# STM32F1_CNC_HW.net
KiCad netlist of a schematic drawn in Altium Designer
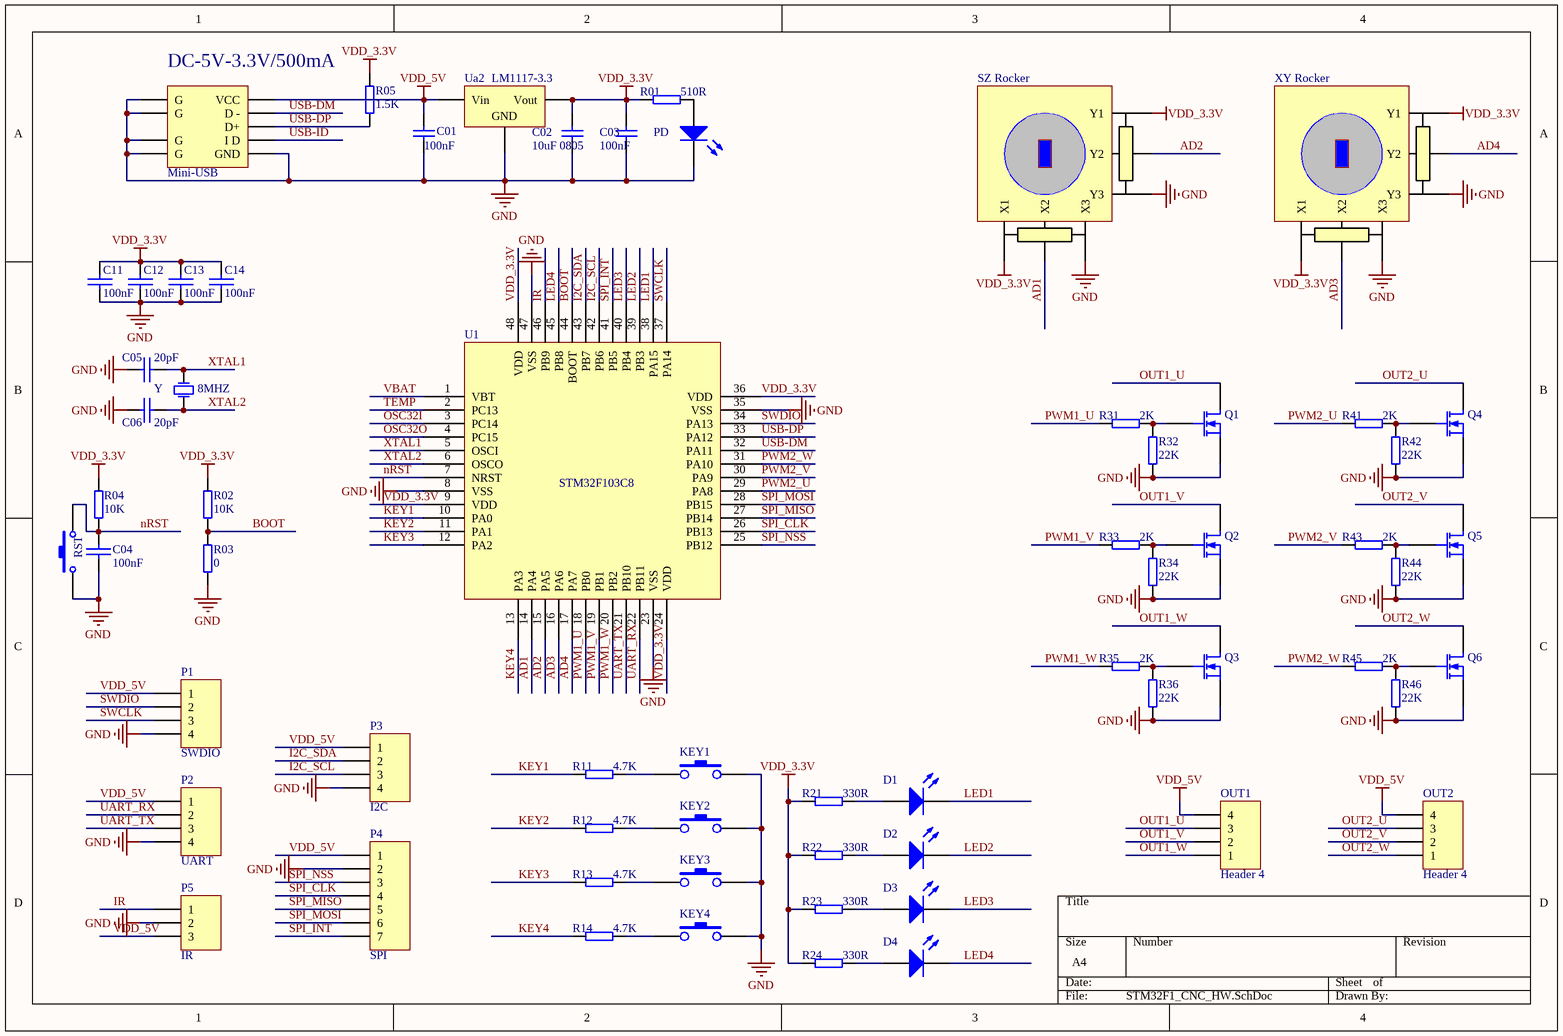
[diagram p0: STM32F1_CNC_HW.SchDoc]

(export (version "E")
  (design (tool "Eeschema 10.0.6"))
  (components
    (comp (ref "C01")
      (value "100nF")
      (footprint "0805")
      (description "0603  X5R")
      (fields (field (name "TOLERANCE") "10%"))
      (libsource (lib "MB963_1") (part "CAP SMD 0603  X5R 1礔 25V 10%"))
    )
    (comp (ref "C02")
      (value "10uF 0805")
      (footprint "0805")
      (description "0603  X5R 1礔")
      (fields (field (name "TOLERANCE") "10%"))
      (libsource (lib "MB963_1") (part "CAP SMD 0603  X5R 1礔 25V 10%"))
    )
    (comp (ref "C03")
      (value "100nF")
      (footprint "0603")
      (description "Capacitor 0402 / 0603 / 0805")
      (libsource (lib "MCD_TOOLS") (part "Capacitor_ST"))
    )
    (comp (ref "C04")
      (value "100nF")
      (footprint "0603")
      (description "Capacitor")
      (libsource (lib "wedolib") (part "CAP"))
    )
    (comp (ref "C05")
      (value "20pF")
      (footprint "0603")
      (description "Capacitor")
      (libsource (lib "wedolib") (part "CAP"))
    )
    (comp (ref "C06")
      (value "20pF")
      (footprint "0603")
      (description "Capacitor")
      (libsource (lib "wedolib") (part "CAP"))
    )
    (comp (ref "C11")
      (value "100nF")
      (footprint "0603")
      (description "Capacitor")
      (libsource (lib "WEDOLIB") (part "CAP"))
    )
    (comp (ref "C12")
      (value "100nF")
      (footprint "0603")
      (description "Capacitor")
      (libsource (lib "WEDOLIB") (part "CAP"))
    )
    (comp (ref "C13")
      (value "100nF")
      (footprint "0603")
      (description "Capacitor")
      (libsource (lib "WEDOLIB") (part "CAP"))
    )
    (comp (ref "C14")
      (value "100nF")
      (footprint "0603")
      (description "Capacitor")
      (libsource (lib "WEDOLIB") (part "CAP"))
    )
    (comp (ref "D1")
      (value "LED0")
      (footprint "LED-0603")
      (description "Typical INFRARED GaAs LED")
      (fields (field (name "PUBLISHER") "Altium Limited"))
      (libsource (lib "Miscellaneous Devices") (part "LED0"))
    )
    (comp (ref "D2")
      (value "LED0")
      (footprint "LED-0603")
      (description "Typical INFRARED GaAs LED")
      (fields (field (name "PUBLISHER") "Altium Limited"))
      (libsource (lib "Miscellaneous Devices") (part "LED0"))
    )
    (comp (ref "D3")
      (value "LED0")
      (footprint "LED-0603")
      (description "Typical INFRARED GaAs LED")
      (fields (field (name "PUBLISHER") "Altium Limited"))
      (libsource (lib "Miscellaneous Devices") (part "LED0"))
    )
    (comp (ref "D4")
      (value "LED0")
      (footprint "LED-0603")
      (description "Typical INFRARED GaAs LED")
      (fields (field (name "PUBLISHER") "Altium Limited"))
      (libsource (lib "Miscellaneous Devices") (part "LED0"))
    )
    (comp (ref "KEY1") (value "微动开关") (footprint "KeyB-6*6") (libsource (lib "STM32F1_CNC_HW") (part "微动开关")))
    (comp (ref "KEY2") (value "微动开关") (footprint "KeyB-6*6") (libsource (lib "STM32F1_CNC_HW") (part "微动开关")))
    (comp (ref "KEY3") (value "微动开关") (footprint "KeyB-6*6") (libsource (lib "STM32F1_CNC_HW") (part "微动开关")))
    (comp (ref "KEY4") (value "微动开关") (footprint "KeyB-6*6") (libsource (lib "STM32F1_CNC_HW") (part "微动开关")))
    (comp (ref "Mini-USB")
      (value "Mini-USB")
      (footprint "USB-mini-S")
      (libsource (lib "STM32F1_CNC_Schlib") (part "Mini-USB_G"))
    )
    (comp (ref "OUT1")
      (value "Header 4")
      (footprint "HDR-2.54-4P")
      (description "Header, 4-Pin")
      (fields (field (name "PUBLISHER") "Altium Limited"))
      (libsource (lib "") (part "Header 4_1"))
    )
    (comp (ref "OUT2")
      (value "Header 4")
      (footprint "HDR-2.54-4P")
      (description "Header, 4-Pin")
      (fields (field (name "PUBLISHER") "Altium Limited"))
      (libsource (lib "") (part "Header 4_1"))
    )
    (comp (ref "P1")
      (value "SWDIO")
      (footprint "HDR-2.54-4P")
      (description "Header, 4-Pin")
      (fields (field (name "PUBLISHER") "Altium Limited"))
      (libsource (lib "Miscellaneous Connectors") (part "Header 4"))
    )
    (comp (ref "P2")
      (value "UART")
      (footprint "HDR-2.54-4P")
      (description "Header, 4-Pin")
      (fields (field (name "PUBLISHER") "Altium Limited"))
      (libsource (lib "Miscellaneous Connectors") (part "Header 4"))
    )
    (comp (ref "P3")
      (value "I2C")
      (footprint "HDR-2.54-4P")
      (description "Header, 4-Pin")
      (fields (field (name "PUBLISHER") "Altium Limited"))
      (libsource (lib "Miscellaneous Connectors") (part "Header 4"))
    )
    (comp (ref "P4")
      (value "SPI")
      (footprint "HDR-2.54-7P")
      (description "Header, 7-Pin")
      (fields (field (name "PUBLISHER") "Altium Limited"))
      (libsource (lib "Miscellaneous Connectors") (part "Header 7"))
    )
    (comp (ref "P5")
      (value "IR")
      (footprint "IR-HS1838")
      (description "Header, 3-Pin")
      (fields (field (name "PUBLISHER") "Altium Limited"))
      (libsource (lib "Miscellaneous Connectors") (part "Header 3"))
    )
    (comp (ref "PD")
      (value "LED")
      (footprint "LED-0603")
      (description "Typical RED, GREEN, YELLOW, AMBER GaAs LED")
      (fields (field (name "PUBLISHER") "Altium Limited"))
      (libsource (lib "Miscellaneous Devices") (part "LED2"))
    )
    (comp (ref "Q1")
      (value "MOSFET-N")
      (footprint "SOT-23")
      (description "N-Channel MOSFET")
      (fields (field (name "PUBLISHER") "Altium Limited"))
      (libsource (lib "Miscellaneous Devices") (part "MOSFET-N"))
    )
    (comp (ref "Q2")
      (value "MOSFET-N")
      (footprint "SOT-23")
      (description "N-Channel MOSFET")
      (fields (field (name "PUBLISHER") "Altium Limited"))
      (libsource (lib "Miscellaneous Devices") (part "MOSFET-N"))
    )
    (comp (ref "Q3")
      (value "MOSFET-N")
      (footprint "SOT-23")
      (description "N-Channel MOSFET")
      (fields (field (name "PUBLISHER") "Altium Limited"))
      (libsource (lib "Miscellaneous Devices") (part "MOSFET-N"))
    )
    (comp (ref "Q4")
      (value "MOSFET-N")
      (footprint "SOT-23")
      (description "N-Channel MOSFET")
      (fields (field (name "PUBLISHER") "Altium Limited"))
      (libsource (lib "Miscellaneous Devices") (part "MOSFET-N"))
    )
    (comp (ref "Q5")
      (value "MOSFET-N")
      (footprint "SOT-23")
      (description "N-Channel MOSFET")
      (fields (field (name "PUBLISHER") "Altium Limited"))
      (libsource (lib "Miscellaneous Devices") (part "MOSFET-N"))
    )
    (comp (ref "Q6")
      (value "MOSFET-N")
      (footprint "SOT-23")
      (description "N-Channel MOSFET")
      (fields (field (name "PUBLISHER") "Altium Limited"))
      (libsource (lib "Miscellaneous Devices") (part "MOSFET-N"))
    )
    (comp (ref "R01")
      (value "510R")
      (footprint "0603")
      (description "Resister")
      (libsource (lib "WEDOLIB") (part "RES1"))
    )
    (comp (ref "R02")
      (value "10K")
      (footprint "0603")
      (description "Resister")
      (libsource (lib "WEDOLIB") (part "RES1"))
    )
    (comp (ref "R03")
      (value "0")
      (footprint "0603")
      (description "Resister")
      (libsource (lib "WEDOLIB") (part "RES1"))
    )
    (comp (ref "R04")
      (value "10K")
      (footprint "0603")
      (description "Resister")
      (libsource (lib "wedolib") (part "RES1"))
    )
    (comp (ref "R05")
      (value "1.5K")
      (footprint "0603")
      (description "Resister")
      (libsource (lib "wedolib") (part "RES1"))
    )
    (comp (ref "R11")
      (value "4.7K")
      (footprint "0603")
      (description "Resister")
      (libsource (lib "WEDOLIB") (part "RES1"))
    )
    (comp (ref "R12")
      (value "4.7K")
      (footprint "0603")
      (description "Resister")
      (libsource (lib "WEDOLIB") (part "RES1"))
    )
    (comp (ref "R13")
      (value "4.7K")
      (footprint "0603")
      (description "Resister")
      (libsource (lib "WEDOLIB") (part "RES1"))
    )
    (comp (ref "R14")
      (value "4.7K")
      (footprint "0603")
      (description "Resister")
      (libsource (lib "WEDOLIB") (part "RES1"))
    )
    (comp (ref "R21")
      (value "330R")
      (footprint "0603")
      (description "Resister")
      (libsource (lib "WEDOLIB") (part "RES1"))
    )
    (comp (ref "R22")
      (value "330R")
      (footprint "0603")
      (description "Resister")
      (libsource (lib "WEDOLIB") (part "RES1"))
    )
    (comp (ref "R23")
      (value "330R")
      (footprint "0603")
      (description "Resister")
      (libsource (lib "WEDOLIB") (part "RES1"))
    )
    (comp (ref "R24")
      (value "330R")
      (footprint "0603")
      (description "Resister")
      (libsource (lib "WEDOLIB") (part "RES1"))
    )
    (comp (ref "R31")
      (value "2K")
      (footprint "0603")
      (description "Resister")
      (libsource (lib "WEDOLIB") (part "RES1"))
    )
    (comp (ref "R32")
      (value "22K")
      (footprint "0603")
      (description "Resister")
      (libsource (lib "WEDOLIB") (part "RES1"))
    )
    (comp (ref "R33")
      (value "2K")
      (footprint "0603")
      (description "Resister")
      (libsource (lib "WEDOLIB") (part "RES1"))
    )
    (comp (ref "R34")
      (value "22K")
      (footprint "0603")
      (description "Resister")
      (libsource (lib "WEDOLIB") (part "RES1"))
    )
    (comp (ref "R35")
      (value "2K")
      (footprint "0603")
      (description "Resister")
      (libsource (lib "WEDOLIB") (part "RES1"))
    )
    (comp (ref "R36")
      (value "22K")
      (footprint "0603")
      (description "Resister")
      (libsource (lib "WEDOLIB") (part "RES1"))
    )
    (comp (ref "R41")
      (value "2K")
      (footprint "0603")
      (description "Resister")
      (libsource (lib "WEDOLIB") (part "RES1"))
    )
    (comp (ref "R42")
      (value "22K")
      (footprint "0603")
      (description "Resister")
      (libsource (lib "WEDOLIB") (part "RES1"))
    )
    (comp (ref "R43")
      (value "2K")
      (footprint "0603")
      (description "Resister")
      (libsource (lib "WEDOLIB") (part "RES1"))
    )
    (comp (ref "R44")
      (value "22K")
      (footprint "0603")
      (description "Resister")
      (libsource (lib "WEDOLIB") (part "RES1"))
    )
    (comp (ref "R45")
      (value "2K")
      (footprint "0603")
      (description "Resister")
      (libsource (lib "WEDOLIB") (part "RES1"))
    )
    (comp (ref "R46")
      (value "22K")
      (footprint "0603")
      (description "Resister")
      (libsource (lib "WEDOLIB") (part "RES1"))
    )
    (comp (ref "RST")
      (value "SW-PB")
      (footprint "RST-6*6")
      (description "Switch")
      (fields (field (name "PUBLISHER") "Altium Limited"))
      (libsource (lib "Miscellaneous Devices") (part "SW-PB"))
    )
    (comp (ref "SZ Rocker")
      (value "XY Rocker")
      (footprint "XY Rocker")
      (libsource (lib "STM32F1_CNC_HW") (part "XY Rocker"))
    )
    (comp (ref "U1")
      (value "STM32F103C8")
      (footprint "QFP48")
      (libsource (lib "STM32F1_CNC_HW") (part "STM32F103C8"))
    )
    (comp (ref "Ua2")
      (value "LM1117-3.3")
      (footprint "SOT223")
      (description "Voltage Regulator")
      (fields (field (name "PUBLISHER") "Altium Limited"))
      (libsource (lib "Miscellaneous Devices") (part "Volt Reg"))
    )
    (comp (ref "XY Rocker")
      (value "XY Rocker")
      (footprint "XY Rocker")
      (libsource (lib "STM32F1_CNC_HW") (part "XY Rocker"))
    )
    (comp (ref "Y")
      (value "8MHZ")
      (footprint "XTAL-3215-3P")
      (description "Crystal Oscillator")
      (fields (field (name "PUBLISHER") "Altium Limited"))
      (libsource (lib "*") (part "ECS-10-13-1"))
    )
  )
  (nets
    (net (code "1") (name "/AD1") (class "Default")
      (node (ref "SZ Rocker") (pin "X2") (pinfunction "X2_X2") (pintype "passive"))
      (node (ref "U1") (pin "14") (pinfunction "PA4_14") (pintype "passive"))
    )
    (net (code "2") (name "/AD2") (class "Default")
      (node (ref "SZ Rocker") (pin "Y2") (pinfunction "Y2_Y2") (pintype "passive"))
      (node (ref "U1") (pin "15") (pinfunction "PA5_15") (pintype "passive"))
    )
    (net (code "3") (name "/AD3") (class "Default")
      (node (ref "U1") (pin "16") (pinfunction "PA6_16") (pintype "passive"))
      (node (ref "XY Rocker") (pin "X2") (pinfunction "X2_X2") (pintype "passive"))
    )
    (net (code "4") (name "/AD4") (class "Default")
      (node (ref "U1") (pin "17") (pinfunction "PA7_17") (pintype "passive"))
      (node (ref "XY Rocker") (pin "Y2") (pinfunction "Y2_Y2") (pintype "passive"))
    )
    (net (code "5") (name "/BOOT") (class "Default")
      (node (ref "R02") (pin "2") (pinfunction "2_2") (pintype "passive"))
      (node (ref "R03") (pin "1") (pinfunction "1_1") (pintype "passive"))
      (node (ref "U1") (pin "44") (pinfunction "BOOT_44") (pintype "passive"))
    )
    (net (code "6") (name "/I2C_SCL") (class "Default")
      (node (ref "P3") (pin "3") (pinfunction "3_3") (pintype "passive"))
      (node (ref "U1") (pin "42") (pinfunction "PB6_42") (pintype "passive"))
    )
    (net (code "7") (name "/I2C_SDA") (class "Default")
      (node (ref "P3") (pin "2") (pinfunction "2_2") (pintype "passive"))
      (node (ref "U1") (pin "43") (pinfunction "PB7_43") (pintype "passive"))
    )
    (net (code "8") (name "/IR") (class "Default")
      (node (ref "P5") (pin "1") (pinfunction "1_1") (pintype "passive"))
      (node (ref "U1") (pin "46") (pinfunction "PB9_46") (pintype "passive"))
    )
    (net (code "9") (name "/KEY1") (class "Default")
      (node (ref "R11") (pin "1") (pinfunction "1_1") (pintype "passive"))
      (node (ref "U1") (pin "10") (pinfunction "PA0_10") (pintype "passive"))
    )
    (net (code "10") (name "/KEY2") (class "Default")
      (node (ref "R12") (pin "1") (pinfunction "1_1") (pintype "passive"))
      (node (ref "U1") (pin "11") (pinfunction "PA1_11") (pintype "passive"))
    )
    (net (code "11") (name "/KEY3") (class "Default")
      (node (ref "R13") (pin "1") (pinfunction "1_1") (pintype "passive"))
      (node (ref "U1") (pin "12") (pinfunction "PA2_12") (pintype "passive"))
    )
    (net (code "12") (name "/KEY4") (class "Default")
      (node (ref "R14") (pin "1") (pinfunction "1_1") (pintype "passive"))
      (node (ref "U1") (pin "13") (pinfunction "PA3_13") (pintype "passive"))
    )
    (net (code "13") (name "/LED1") (class "Default")
      (node (ref "D1") (pin "2") (pinfunction "K_2") (pintype "passive"))
      (node (ref "U1") (pin "38") (pinfunction "PA15_38") (pintype "passive"))
    )
    (net (code "14") (name "/LED2") (class "Default")
      (node (ref "D2") (pin "2") (pinfunction "K_2") (pintype "passive"))
      (node (ref "U1") (pin "39") (pinfunction "PB3_39") (pintype "passive"))
    )
    (net (code "15") (name "/LED3") (class "Default")
      (node (ref "D3") (pin "2") (pinfunction "K_2") (pintype "passive"))
      (node (ref "U1") (pin "40") (pinfunction "PB4_40") (pintype "passive"))
    )
    (net (code "16") (name "/LED4") (class "Default")
      (node (ref "D4") (pin "2") (pinfunction "K_2") (pintype "passive"))
      (node (ref "U1") (pin "45") (pinfunction "PB8_45") (pintype "passive"))
    )
    (net (code "17") (name "/OSC32I") (class "Default")
      (node (ref "U1") (pin "3") (pinfunction "PC14_3") (pintype "passive"))
    )
    (net (code "18") (name "/OSC32O") (class "Default")
      (node (ref "U1") (pin "4") (pinfunction "PC15_4") (pintype "passive"))
    )
    (net (code "19") (name "/OUT1_U") (class "Default")
      (node (ref "OUT1") (pin "3") (pinfunction "3_3") (pintype "passive"))
      (node (ref "Q1") (pin "3") (pinfunction "D_3") (pintype "passive"))
    )
    (net (code "20") (name "/OUT1_V") (class "Default")
      (node (ref "OUT1") (pin "2") (pinfunction "2_2") (pintype "passive"))
      (node (ref "Q2") (pin "3") (pinfunction "D_3") (pintype "passive"))
    )
    (net (code "21") (name "/OUT1_W") (class "Default")
      (node (ref "OUT1") (pin "1") (pinfunction "1_1") (pintype "passive"))
      (node (ref "Q3") (pin "3") (pinfunction "D_3") (pintype "passive"))
    )
    (net (code "22") (name "/OUT2_U") (class "Default")
      (node (ref "OUT2") (pin "3") (pinfunction "3_3") (pintype "passive"))
      (node (ref "Q4") (pin "3") (pinfunction "D_3") (pintype "passive"))
    )
    (net (code "23") (name "/OUT2_V") (class "Default")
      (node (ref "OUT2") (pin "2") (pinfunction "2_2") (pintype "passive"))
      (node (ref "Q5") (pin "3") (pinfunction "D_3") (pintype "passive"))
    )
    (net (code "24") (name "/OUT2_W") (class "Default")
      (node (ref "OUT2") (pin "1") (pinfunction "1_1") (pintype "passive"))
      (node (ref "Q6") (pin "3") (pinfunction "D_3") (pintype "passive"))
    )
    (net (code "25") (name "/PWM1_U") (class "Default")
      (node (ref "R31") (pin "1") (pinfunction "1_1") (pintype "passive"))
      (node (ref "U1") (pin "18") (pinfunction "PB0_18") (pintype "passive"))
    )
    (net (code "26") (name "/PWM1_V") (class "Default")
      (node (ref "R33") (pin "1") (pinfunction "1_1") (pintype "passive"))
      (node (ref "U1") (pin "19") (pinfunction "PB1_19") (pintype "passive"))
    )
    (net (code "27") (name "/PWM1_W") (class "Default")
      (node (ref "R35") (pin "1") (pinfunction "1_1") (pintype "passive"))
      (node (ref "U1") (pin "20") (pinfunction "PB2_20") (pintype "passive"))
    )
    (net (code "28") (name "/PWM2_U") (class "Default")
      (node (ref "R41") (pin "1") (pinfunction "1_1") (pintype "passive"))
      (node (ref "U1") (pin "29") (pinfunction "PA8_29") (pintype "passive"))
    )
    (net (code "29") (name "/PWM2_V") (class "Default")
      (node (ref "R43") (pin "1") (pinfunction "1_1") (pintype "passive"))
      (node (ref "U1") (pin "30") (pinfunction "PA9_30") (pintype "passive"))
    )
    (net (code "30") (name "/PWM2_W") (class "Default")
      (node (ref "R45") (pin "1") (pinfunction "1_1") (pintype "passive"))
      (node (ref "U1") (pin "31") (pinfunction "PA10_31") (pintype "passive"))
    )
    (net (code "31") (name "/SPI_CLK") (class "Default")
      (node (ref "P4") (pin "4") (pinfunction "4_4") (pintype "passive"))
      (node (ref "U1") (pin "26") (pinfunction "PB13_26") (pintype "passive"))
    )
    (net (code "32") (name "/SPI_INT") (class "Default")
      (node (ref "P4") (pin "7") (pinfunction "7_7") (pintype "passive"))
      (node (ref "U1") (pin "41") (pinfunction "PB5_41") (pintype "passive"))
    )
    (net (code "33") (name "/SPI_MISO") (class "Default")
      (node (ref "P4") (pin "5") (pinfunction "5_5") (pintype "passive"))
      (node (ref "U1") (pin "27") (pinfunction "PB14_27") (pintype "passive"))
    )
    (net (code "34") (name "/SPI_MOSI") (class "Default")
      (node (ref "P4") (pin "6") (pinfunction "6_6") (pintype "passive"))
      (node (ref "U1") (pin "28") (pinfunction "PB15_28") (pintype "passive"))
    )
    (net (code "35") (name "/SPI_NSS") (class "Default")
      (node (ref "P4") (pin "3") (pinfunction "3_3") (pintype "passive"))
      (node (ref "U1") (pin "25") (pinfunction "PB12_25") (pintype "passive"))
    )
    (net (code "36") (name "/SWCLK") (class "Default")
      (node (ref "P1") (pin "3") (pinfunction "3_3") (pintype "passive"))
      (node (ref "U1") (pin "37") (pinfunction "PA14_37") (pintype "passive"))
    )
    (net (code "37") (name "/SWDIO") (class "Default")
      (node (ref "P1") (pin "2") (pinfunction "2_2") (pintype "passive"))
      (node (ref "U1") (pin "34") (pinfunction "PA13_34") (pintype "passive"))
    )
    (net (code "38") (name "/TEMP") (class "Default")
      (node (ref "U1") (pin "2") (pinfunction "PC13_2") (pintype "passive"))
    )
    (net (code "39") (name "/UART_RX") (class "Default")
      (node (ref "P2") (pin "2") (pinfunction "2_2") (pintype "passive"))
      (node (ref "U1") (pin "22") (pinfunction "PB11_22") (pintype "passive"))
    )
    (net (code "40") (name "/UART_TX") (class "Default")
      (node (ref "P2") (pin "3") (pinfunction "3_3") (pintype "passive"))
      (node (ref "U1") (pin "21") (pinfunction "PB10_21") (pintype "passive"))
    )
    (net (code "41") (name "/USB-DM") (class "Default")
      (node (ref "Mini-USB") (pin "2") (pinfunction "D_-_2") (pintype "passive"))
      (node (ref "U1") (pin "32") (pinfunction "PA11_32") (pintype "passive"))
    )
    (net (code "42") (name "/USB-DP") (class "Default")
      (node (ref "Mini-USB") (pin "3") (pinfunction "D+_3") (pintype "passive"))
      (node (ref "R05") (pin "2") (pinfunction "2_2") (pintype "passive"))
      (node (ref "U1") (pin "33") (pinfunction "PA12_33") (pintype "passive"))
    )
    (net (code "43") (name "/USB-ID") (class "Default")
      (node (ref "Mini-USB") (pin "4") (pinfunction "I_D_4") (pintype "passive"))
    )
    (net (code "44") (name "/VBAT") (class "Default")
      (node (ref "U1") (pin "1") (pinfunction "VBT_1") (pintype "passive"))
    )
    (net (code "45") (name "/XTAL1") (class "Default")
      (node (ref "C05") (pin "2") (pinfunction "2_2") (pintype "passive"))
      (node (ref "U1") (pin "5") (pinfunction "OSCI_5") (pintype "passive"))
      (node (ref "Y") (pin "3") (pinfunction "OSC2_3") (pintype "passive"))
    )
    (net (code "46") (name "/XTAL2") (class "Default")
      (node (ref "C06") (pin "2") (pinfunction "2_2") (pintype "passive"))
      (node (ref "U1") (pin "6") (pinfunction "OSCO_6") (pintype "passive"))
      (node (ref "Y") (pin "1") (pinfunction "OSC1_1") (pintype "passive"))
    )
    (net (code "47") (name "/nRST") (class "Default")
      (node (ref "C04") (pin "1") (pinfunction "1_1") (pintype "passive"))
      (node (ref "R04") (pin "2") (pinfunction "2_2") (pintype "passive"))
      (node (ref "RST") (pin "1") (pinfunction "1_1") (pintype "passive"))
      (node (ref "U1") (pin "7") (pinfunction "NRST_7") (pintype "passive"))
    )
    (net (code "48") (name "GND") (class "Default")
      (node (ref "C01") (pin "1") (pinfunction "1_1") (pintype "passive"))
      (node (ref "C02") (pin "2") (pinfunction "2_2") (pintype "passive"))
      (node (ref "C03") (pin "1") (pinfunction "1_1") (pintype "passive"))
      (node (ref "C04") (pin "2") (pinfunction "2_2") (pintype "passive"))
      (node (ref "C05") (pin "1") (pinfunction "1_1") (pintype "passive"))
      (node (ref "C06") (pin "1") (pinfunction "1_1") (pintype "passive"))
      (node (ref "C11") (pin "2") (pinfunction "2_2") (pintype "passive"))
      (node (ref "C12") (pin "2") (pinfunction "2_2") (pintype "passive"))
      (node (ref "C13") (pin "2") (pinfunction "2_2") (pintype "passive"))
      (node (ref "C14") (pin "2") (pinfunction "2_2") (pintype "passive"))
      (node (ref "KEY1") (pin "2") (pinfunction "2_2") (pintype "passive"))
      (node (ref "KEY2") (pin "2") (pinfunction "2_2") (pintype "passive"))
      (node (ref "KEY3") (pin "2") (pinfunction "2_2") (pintype "passive"))
      (node (ref "KEY4") (pin "2") (pinfunction "2_2") (pintype "passive"))
      (node (ref "Mini-USB") (pin "0") (pinfunction "G_0") (pintype "passive"))
      (node (ref "Mini-USB") (pin "5") (pinfunction "GND_5") (pintype "passive"))
      (node (ref "P1") (pin "4") (pinfunction "4_4") (pintype "passive"))
      (node (ref "P2") (pin "4") (pinfunction "4_4") (pintype "passive"))
      (node (ref "P3") (pin "4") (pinfunction "4_4") (pintype "passive"))
      (node (ref "P4") (pin "2") (pinfunction "2_2") (pintype "passive"))
      (node (ref "P5") (pin "2") (pinfunction "2_2") (pintype "passive"))
      (node (ref "PD") (pin "2") (pinfunction "K_2") (pintype "passive"))
      (node (ref "Q1") (pin "2") (pinfunction "S_2") (pintype "passive"))
      (node (ref "Q2") (pin "2") (pinfunction "S_2") (pintype "passive"))
      (node (ref "Q3") (pin "2") (pinfunction "S_2") (pintype "passive"))
      (node (ref "Q4") (pin "2") (pinfunction "S_2") (pintype "passive"))
      (node (ref "Q5") (pin "2") (pinfunction "S_2") (pintype "passive"))
      (node (ref "Q6") (pin "2") (pinfunction "S_2") (pintype "passive"))
      (node (ref "R03") (pin "2") (pinfunction "2_2") (pintype "passive"))
      (node (ref "R32") (pin "1") (pinfunction "1_1") (pintype "passive"))
      (node (ref "R34") (pin "1") (pinfunction "1_1") (pintype "passive"))
      (node (ref "R36") (pin "1") (pinfunction "1_1") (pintype "passive"))
      (node (ref "R42") (pin "1") (pinfunction "1_1") (pintype "passive"))
      (node (ref "R44") (pin "1") (pinfunction "1_1") (pintype "passive"))
      (node (ref "R46") (pin "1") (pinfunction "1_1") (pintype "passive"))
      (node (ref "RST") (pin "2") (pinfunction "2_2") (pintype "passive"))
      (node (ref "SZ Rocker") (pin "X3") (pinfunction "X3_X3") (pintype "passive"))
      (node (ref "SZ Rocker") (pin "Y3") (pinfunction "Y3_Y3") (pintype "passive"))
      (node (ref "U1") (pin "23") (pinfunction "VSS_23") (pintype "passive"))
      (node (ref "U1") (pin "35") (pinfunction "VSS_35") (pintype "passive"))
      (node (ref "U1") (pin "47") (pinfunction "VSS_47") (pintype "passive"))
      (node (ref "U1") (pin "8") (pinfunction "VSS_8") (pintype "passive"))
      (node (ref "Ua2") (pin "1") (pinfunction "GND_1") (pintype "passive"))
      (node (ref "XY Rocker") (pin "X3") (pinfunction "X3_X3") (pintype "passive"))
      (node (ref "XY Rocker") (pin "Y3") (pinfunction "Y3_Y3") (pintype "passive"))
    )
    (net (code "49") (name "Net-(D1-A)") (class "Default")
      (node (ref "D1") (pin "1") (pinfunction "A_1") (pintype "passive"))
      (node (ref "R21") (pin "2") (pinfunction "2_2") (pintype "passive"))
    )
    (net (code "50") (name "Net-(D2-A)") (class "Default")
      (node (ref "D2") (pin "1") (pinfunction "A_1") (pintype "passive"))
      (node (ref "R22") (pin "2") (pinfunction "2_2") (pintype "passive"))
    )
    (net (code "51") (name "Net-(D3-A)") (class "Default")
      (node (ref "D3") (pin "1") (pinfunction "A_1") (pintype "passive"))
      (node (ref "R23") (pin "2") (pinfunction "2_2") (pintype "passive"))
    )
    (net (code "52") (name "Net-(D4-A)") (class "Default")
      (node (ref "D4") (pin "1") (pinfunction "A_1") (pintype "passive"))
      (node (ref "R24") (pin "2") (pinfunction "2_2") (pintype "passive"))
    )
    (net (code "53") (name "Net-(KEY1-Pad1)") (class "Default")
      (node (ref "KEY1") (pin "1") (pinfunction "1_1") (pintype "passive"))
      (node (ref "R11") (pin "2") (pinfunction "2_2") (pintype "passive"))
    )
    (net (code "54") (name "Net-(KEY2-Pad1)") (class "Default")
      (node (ref "KEY2") (pin "1") (pinfunction "1_1") (pintype "passive"))
      (node (ref "R12") (pin "2") (pinfunction "2_2") (pintype "passive"))
    )
    (net (code "55") (name "Net-(KEY3-Pad1)") (class "Default")
      (node (ref "KEY3") (pin "1") (pinfunction "1_1") (pintype "passive"))
      (node (ref "R13") (pin "2") (pinfunction "2_2") (pintype "passive"))
    )
    (net (code "56") (name "Net-(KEY4-Pad1)") (class "Default")
      (node (ref "KEY4") (pin "1") (pinfunction "1_1") (pintype "passive"))
      (node (ref "R14") (pin "2") (pinfunction "2_2") (pintype "passive"))
    )
    (net (code "57") (name "Net-(PD-A)") (class "Default")
      (node (ref "PD") (pin "1") (pinfunction "A_1") (pintype "passive"))
      (node (ref "R01") (pin "1") (pinfunction "1_1") (pintype "passive"))
    )
    (net (code "58") (name "Net-(Q1-G)") (class "Default")
      (node (ref "Q1") (pin "1") (pinfunction "G_1") (pintype "passive"))
      (node (ref "R31") (pin "2") (pinfunction "2_2") (pintype "passive"))
      (node (ref "R32") (pin "2") (pinfunction "2_2") (pintype "passive"))
    )
    (net (code "59") (name "Net-(Q2-G)") (class "Default")
      (node (ref "Q2") (pin "1") (pinfunction "G_1") (pintype "passive"))
      (node (ref "R33") (pin "2") (pinfunction "2_2") (pintype "passive"))
      (node (ref "R34") (pin "2") (pinfunction "2_2") (pintype "passive"))
    )
    (net (code "60") (name "Net-(Q3-G)") (class "Default")
      (node (ref "Q3") (pin "1") (pinfunction "G_1") (pintype "passive"))
      (node (ref "R35") (pin "2") (pinfunction "2_2") (pintype "passive"))
      (node (ref "R36") (pin "2") (pinfunction "2_2") (pintype "passive"))
    )
    (net (code "61") (name "Net-(Q4-G)") (class "Default")
      (node (ref "Q4") (pin "1") (pinfunction "G_1") (pintype "passive"))
      (node (ref "R41") (pin "2") (pinfunction "2_2") (pintype "passive"))
      (node (ref "R42") (pin "2") (pinfunction "2_2") (pintype "passive"))
    )
    (net (code "62") (name "Net-(Q5-G)") (class "Default")
      (node (ref "Q5") (pin "1") (pinfunction "G_1") (pintype "passive"))
      (node (ref "R43") (pin "2") (pinfunction "2_2") (pintype "passive"))
      (node (ref "R44") (pin "2") (pinfunction "2_2") (pintype "passive"))
    )
    (net (code "63") (name "Net-(Q6-G)") (class "Default")
      (node (ref "Q6") (pin "1") (pinfunction "G_1") (pintype "passive"))
      (node (ref "R45") (pin "2") (pinfunction "2_2") (pintype "passive"))
      (node (ref "R46") (pin "2") (pinfunction "2_2") (pintype "passive"))
    )
    (net (code "64") (name "VDD_3.3V") (class "Default")
      (node (ref "C02") (pin "1") (pinfunction "1_1") (pintype "passive"))
      (node (ref "C03") (pin "2") (pinfunction "2_2") (pintype "passive"))
      (node (ref "C11") (pin "1") (pinfunction "1_1") (pintype "passive"))
      (node (ref "C12") (pin "1") (pinfunction "1_1") (pintype "passive"))
      (node (ref "C13") (pin "1") (pinfunction "1_1") (pintype "passive"))
      (node (ref "C14") (pin "1") (pinfunction "1_1") (pintype "passive"))
      (node (ref "R01") (pin "2") (pinfunction "2_2") (pintype "passive"))
      (node (ref "R02") (pin "1") (pinfunction "1_1") (pintype "passive"))
      (node (ref "R04") (pin "1") (pinfunction "1_1") (pintype "passive"))
      (node (ref "R05") (pin "1") (pinfunction "1_1") (pintype "passive"))
      (node (ref "R21") (pin "1") (pinfunction "1_1") (pintype "passive"))
      (node (ref "R22") (pin "1") (pinfunction "1_1") (pintype "passive"))
      (node (ref "R23") (pin "1") (pinfunction "1_1") (pintype "passive"))
      (node (ref "R24") (pin "1") (pinfunction "1_1") (pintype "passive"))
      (node (ref "SZ Rocker") (pin "X1") (pinfunction "X1_X1") (pintype "passive"))
      (node (ref "SZ Rocker") (pin "Y1") (pinfunction "Y1_Y1") (pintype "passive"))
      (node (ref "U1") (pin "24") (pinfunction "VDD_24") (pintype "passive"))
      (node (ref "U1") (pin "36") (pinfunction "VDD_36") (pintype "passive"))
      (node (ref "U1") (pin "48") (pinfunction "VDD_48") (pintype "passive"))
      (node (ref "U1") (pin "9") (pinfunction "VDD_9") (pintype "passive"))
      (node (ref "Ua2") (pin "2") (pinfunction "Vout_2") (pintype "passive"))
      (node (ref "XY Rocker") (pin "X1") (pinfunction "X1_X1") (pintype "passive"))
      (node (ref "XY Rocker") (pin "Y1") (pinfunction "Y1_Y1") (pintype "passive"))
    )
    (net (code "65") (name "VDD_5V") (class "Default")
      (node (ref "C01") (pin "2") (pinfunction "2_2") (pintype "passive"))
      (node (ref "Mini-USB") (pin "1") (pinfunction "VCC_1") (pintype "passive"))
      (node (ref "OUT1") (pin "4") (pinfunction "4_4") (pintype "passive"))
      (node (ref "OUT2") (pin "4") (pinfunction "4_4") (pintype "passive"))
      (node (ref "P1") (pin "1") (pinfunction "1_1") (pintype "passive"))
      (node (ref "P2") (pin "1") (pinfunction "1_1") (pintype "passive"))
      (node (ref "P3") (pin "1") (pinfunction "1_1") (pintype "passive"))
      (node (ref "P4") (pin "1") (pinfunction "1_1") (pintype "passive"))
      (node (ref "P5") (pin "3") (pinfunction "3_3") (pintype "passive"))
      (node (ref "Ua2") (pin "3") (pinfunction "Vin_3") (pintype "passive"))
    )
  )
)
